# W25Q128.net
KiCad netlist of a schematic drawn in Altium Designer
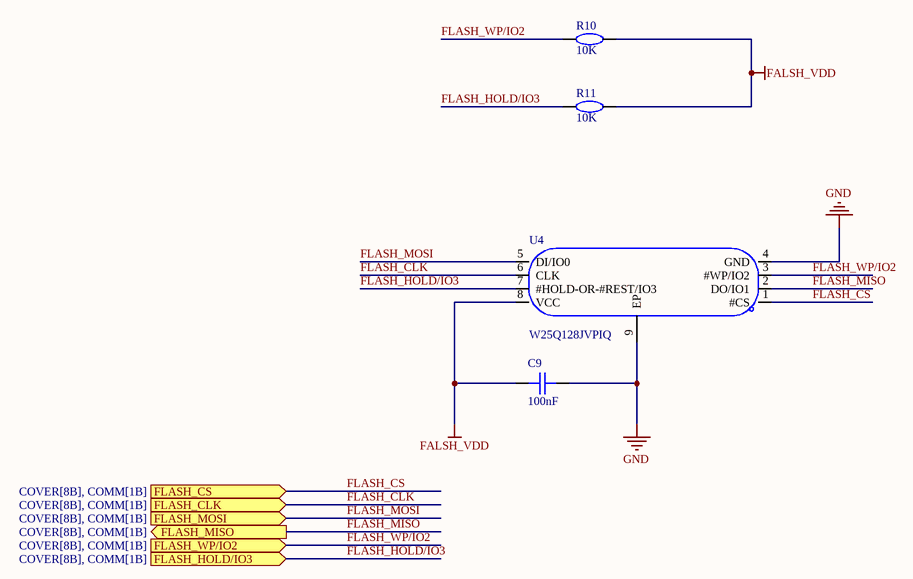
[diagram p0: W25Q128.SchDoc]

(export (version "E")
  (design (tool "Eeschema 10.0.6"))
  (components
    (comp (ref "C9")
      (value "100nF")
      (footprint "C0402")
      (fields (field (name "NAME") "100nF"))
      (libsource (lib "my_library") (part "CAP_0402"))
    )
    (comp (ref "R10")
      (value "10K")
      (footprint "R0402")
      (fields (field (name "NAME") "10K"))
      (libsource (lib "my_library") (part "Res_0402"))
    )
    (comp (ref "R11")
      (value "10K")
      (footprint "R0402")
      (fields (field (name "NAME") "10K"))
      (libsource (lib "my_library") (part "Res_0402"))
    )
    (comp (ref "U4")
      (value "W25Q128JVPIQ")
      (footprint "WSON-8_L6.0-W5.0-P1.27-BL-EP")
      (fields (field (name "MANUFACTURER") "WINBOND(华邦)") (field (name "NAME") "W25Q128JVPIQ"))
      (libsource (lib "my_library") (part "W25Q128JVPIQ_C190862"))
    )
  )
  (nets
    (net (code "1") (name "/FLASH_CLK") (class "Default")
      (node (ref "U4") (pin "6") (pinfunction "CLK_6") (pintype "passive"))
    )
    (net (code "2") (name "/FLASH_CS") (class "Default")
      (node (ref "U4") (pin "1") (pinfunction "#CS_1") (pintype "passive"))
    )
    (net (code "3") (name "/FLASH_HOLD{slash}IO3") (class "Default")
      (node (ref "R11") (pin "1") (pinfunction "1_1") (pintype "passive"))
      (node (ref "U4") (pin "7") (pinfunction "#HOLD-OR-#REST/IO3_7") (pintype "passive"))
    )
    (net (code "4") (name "/FLASH_MISO") (class "Default")
      (node (ref "U4") (pin "2") (pinfunction "DO/IO1_2") (pintype "passive"))
    )
    (net (code "5") (name "/FLASH_MOSI") (class "Default")
      (node (ref "U4") (pin "5") (pinfunction "DI/IO0_5") (pintype "passive"))
    )
    (net (code "6") (name "/FLASH_WP{slash}IO2") (class "Default")
      (node (ref "R10") (pin "1") (pinfunction "1_1") (pintype "passive"))
      (node (ref "U4") (pin "3") (pinfunction "#WP/IO2_3") (pintype "passive"))
    )
    (net (code "7") (name "FALSH_VDD") (class "Default")
      (node (ref "C9") (pin "1") (pinfunction "1_1") (pintype "passive"))
      (node (ref "R10") (pin "2") (pinfunction "2_2") (pintype "passive"))
      (node (ref "R11") (pin "2") (pinfunction "2_2") (pintype "passive"))
      (node (ref "U4") (pin "8") (pinfunction "VCC_8") (pintype "passive"))
    )
    (net (code "8") (name "GND") (class "Default")
      (node (ref "C9") (pin "2") (pinfunction "2_2") (pintype "passive"))
      (node (ref "U4") (pin "4") (pinfunction "GND_4") (pintype "passive"))
      (node (ref "U4") (pin "9") (pinfunction "EP_9") (pintype "passive"))
    )
  )
)
